# Interface.net
KiCad netlist of a schematic drawn in Altium Designer
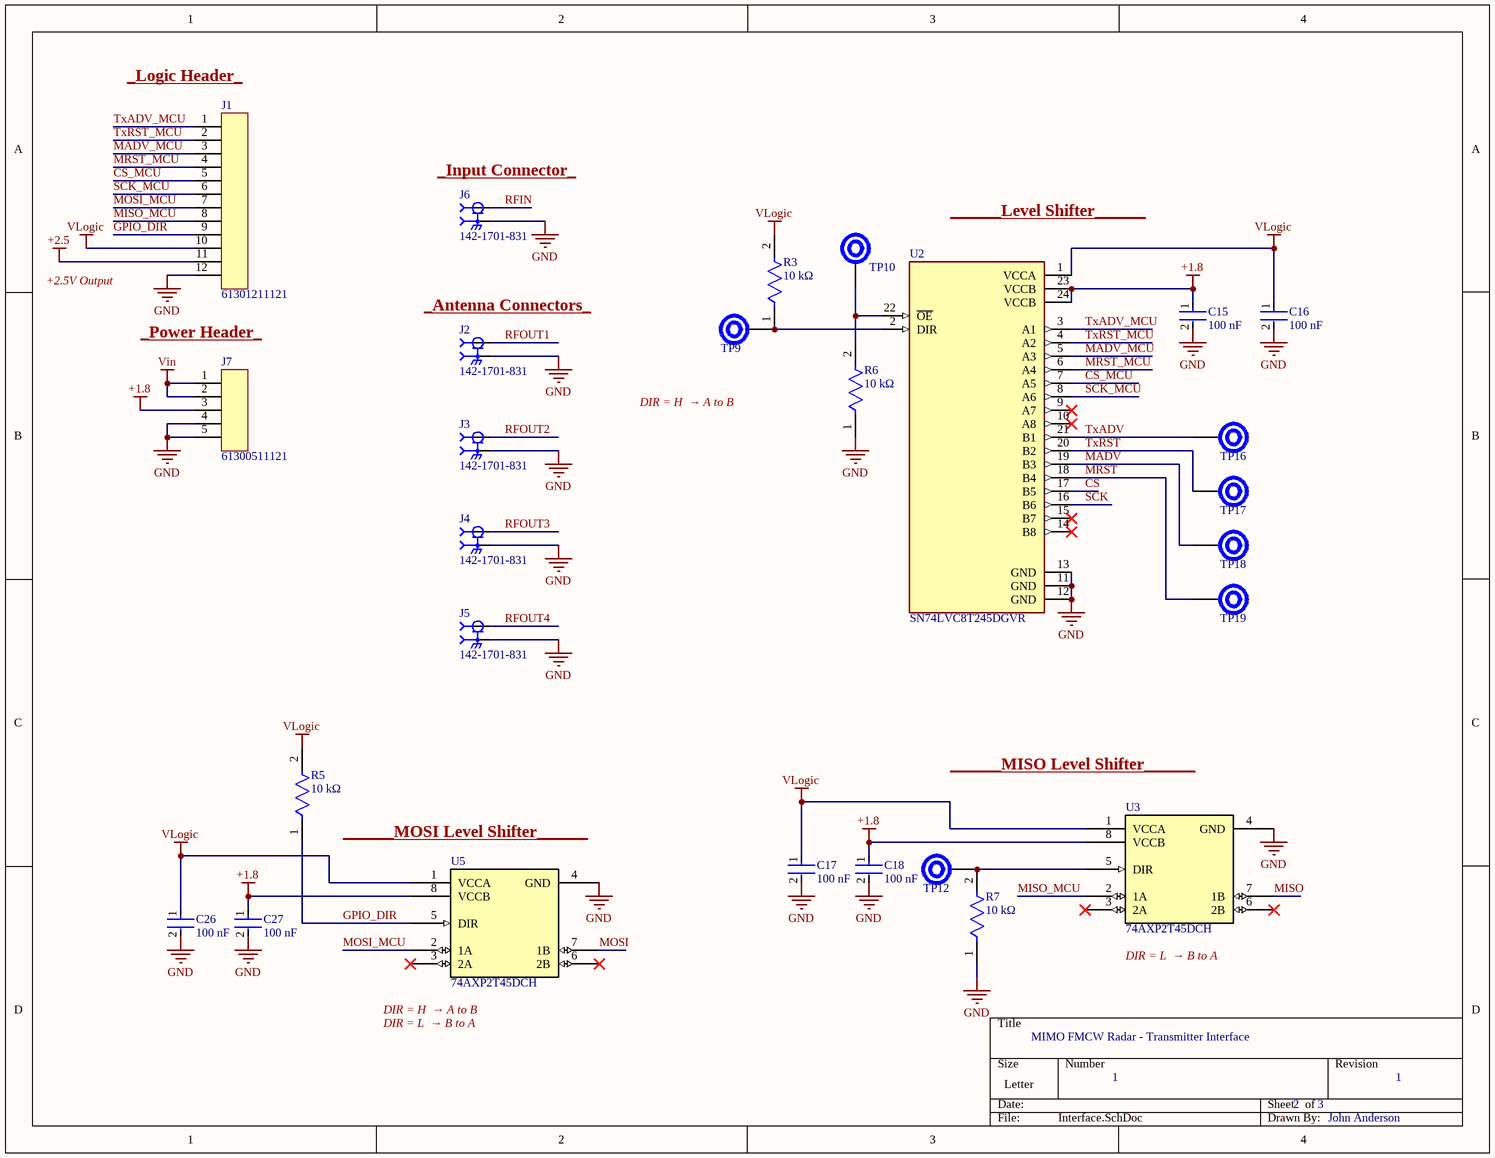
[diagram p0: Interface.SchDoc]

(export (version "E")
  (design (tool "Eeschema 10.0.6"))
  (components
    (comp (ref "C15")
      (value "100 nF")
      (footprint "FP-CGA3E-0_3-0_1-MFG")
      (libsource (lib "Power Pullers") (part "b4654b650e69147ec39a6b967a45e02"))
    )
    (comp (ref "C16")
      (value "100 nF")
      (footprint "FP-CGA3E-0_3-0_1-MFG")
      (libsource (lib "Power Pullers") (part "b4654b650e69147ec39a6b967a45e02"))
    )
    (comp (ref "C17")
      (value "100 nF")
      (footprint "FP-CGA3E-0_3-0_1-MFG")
      (libsource (lib "Power Pullers") (part "b4654b650e69147ec39a6b967a45e02"))
    )
    (comp (ref "C18")
      (value "100 nF")
      (footprint "FP-CGA3E-0_3-0_1-MFG")
      (libsource (lib "Power Pullers") (part "b4654b650e69147ec39a6b967a45e02"))
    )
    (comp (ref "C26")
      (value "100 nF")
      (footprint "FP-CGA3E-0_3-0_1-MFG")
      (libsource (lib "Power Pullers") (part "b4654b650e69147ec39a6b967a45e02"))
    )
    (comp (ref "C27")
      (value "100 nF")
      (footprint "FP-CGA3E-0_3-0_1-MFG")
      (libsource (lib "Power Pullers") (part "b4654b650e69147ec39a6b967a45e02"))
    )
    (comp (ref "J1")
      (value "61301211121")
      (footprint "61301211121")
      (description "THT Vertical Pin Header WR-PHD, Pitch 2.54 mm, Single Row, 12 pins")
      (libsource (lib "Power Pullers") (part "Header_Male_1R_12P"))
    )
    (comp (ref "J2")
      (value "142-1701-831")
      (footprint "142-1701-831-Footprint-1")
      (description "RF SMA Connector, 1 Contact(s), Female, Board Mount, Surface Mount Terminal, Locking, Jack")
      (libsource (lib "Power Pullers") (part "142-1701-831-Symbol-1"))
    )
    (comp (ref "J3")
      (value "142-1701-831")
      (footprint "142-1701-831-Footprint-1")
      (description "RF SMA Connector, 1 Contact(s), Female, Board Mount, Surface Mount Terminal, Locking, Jack")
      (libsource (lib "Power Pullers") (part "142-1701-831-Symbol-1"))
    )
    (comp (ref "J4")
      (value "142-1701-831")
      (footprint "142-1701-831-Footprint-1")
      (description "RF SMA Connector, 1 Contact(s), Female, Board Mount, Surface Mount Terminal, Locking, Jack")
      (libsource (lib "Power Pullers") (part "142-1701-831-Symbol-1"))
    )
    (comp (ref "J5")
      (value "142-1701-831")
      (footprint "142-1701-831-Footprint-1")
      (description "RF SMA Connector, 1 Contact(s), Female, Board Mount, Surface Mount Terminal, Locking, Jack")
      (libsource (lib "Power Pullers") (part "142-1701-831-Symbol-1"))
    )
    (comp (ref "J6")
      (value "142-1701-831")
      (footprint "142-1701-831-Footprint-1")
      (description "RF SMA Connector, 1 Contact(s), Female, Board Mount, Surface Mount Terminal, Locking, Jack")
      (libsource (lib "Power Pullers") (part "142-1701-831-Symbol-1"))
    )
    (comp (ref "J7")
      (value "61300511121")
      (footprint "61300511121")
      (description "THT Vertical Pin Header WR-PHD, Pitch 2.54 mm, Single Row, 5 pins")
      (libsource (lib "Power Pullers") (part "Header_Male_1R_05P"))
    )
    (comp (ref "R3")
      (value "10 kΩ")
      (footprint "FP-RC0603-0_55-IPC_C")
      (fields (field (name "POWER") "100mW") (field (name "TOLERANCE") "1%"))
      (libsource (lib "Power Pullers") (part "1029c3af85768c4190bb7ad29bc67b5"))
    )
    (comp (ref "R5")
      (value "10 kΩ")
      (footprint "FP-RC0603-0_55-IPC_C")
      (fields (field (name "POWER") "100mW") (field (name "TOLERANCE") "1%"))
      (libsource (lib "Power Pullers") (part "1029c3af85768c4190bb7ad29bc67b5"))
    )
    (comp (ref "R6")
      (value "10 kΩ")
      (footprint "FP-RC0603-0_55-IPC_C")
      (fields (field (name "POWER") "100mW") (field (name "TOLERANCE") "1%"))
      (libsource (lib "Power Pullers") (part "1029c3af85768c4190bb7ad29bc67b5"))
    )
    (comp (ref "R7")
      (value "10 kΩ")
      (footprint "FP-RC0603-0_55-IPC_C")
      (fields (field (name "POWER") "100mW") (field (name "TOLERANCE") "1%"))
      (libsource (lib "Power Pullers") (part "1029c3af85768c4190bb7ad29bc67b5"))
    )
    (comp (ref "TP9")
      (value "Test Point - 32 mil")
      (footprint "Test Point - 32 mil-Footprint-1")
      (description "32 mil (0.8 mm) test point.")
      (libsource (lib "Power Pullers") (part "Test Point - 32 mil-Symbol-1"))
    )
    (comp (ref "TP10")
      (value "Test Point - 32 mil")
      (footprint "Test Point - 32 mil-Footprint-1")
      (description "32 mil (0.8 mm) test point.")
      (libsource (lib "Power Pullers") (part "Test Point - 32 mil-Symbol-1"))
    )
    (comp (ref "TP12")
      (value "Test Point - 32 mil")
      (footprint "Test Point - 32 mil-Footprint-1")
      (description "32 mil (0.8 mm) test point.")
      (libsource (lib "Power Pullers") (part "Test Point - 32 mil-Symbol-1"))
    )
    (comp (ref "TP16")
      (value "Test Point - 32 mil")
      (footprint "Test Point - 32 mil-Footprint-1")
      (description "32 mil (0.8 mm) test point.")
      (libsource (lib "Power Pullers") (part "Test Point - 32 mil-Symbol-1"))
    )
    (comp (ref "TP17")
      (value "Test Point - 32 mil")
      (footprint "Test Point - 32 mil-Footprint-1")
      (description "32 mil (0.8 mm) test point.")
      (libsource (lib "Power Pullers") (part "Test Point - 32 mil-Symbol-1"))
    )
    (comp (ref "TP18")
      (value "Test Point - 32 mil")
      (footprint "Test Point - 32 mil-Footprint-1")
      (description "32 mil (0.8 mm) test point.")
      (libsource (lib "Power Pullers") (part "Test Point - 32 mil-Symbol-1"))
    )
    (comp (ref "TP19")
      (value "Test Point - 32 mil")
      (footprint "Test Point - 32 mil-Footprint-1")
      (description "32 mil (0.8 mm) test point.")
      (libsource (lib "Power Pullers") (part "Test Point - 32 mil-Symbol-1"))
    )
    (comp (ref "U2")
      (value "SN74LVC8T245DGVR")
      (footprint "SN74LVC8T245DGVR-Footprint-1")
      (description "IC BUS TRANSCVR 8BIT 24TVSOP / Voltage Level Translator 8-CH Bidirectional 24-Pin TVSOP T/R")
      (libsource (lib "Power Pullers") (part "SN74LVC8T245DGVR-Symbol-1"))
    )
    (comp (ref "U3")
      (value "74AXP2T45DCH")
      (footprint "74AXP2T45DCH-Footprint-1")
      (description "Dual Supply Level Translator 2-bit Bidirectional 0.95V to 5.5V 8-Pin VSSOP")
      (libsource (lib "Power Pullers") (part "74AXP2T45DCH-Symbol-1"))
    )
    (comp (ref "U5")
      (value "74AXP2T45DCH")
      (footprint "74AXP2T45DCH-Footprint-1")
      (description "Dual Supply Level Translator 2-bit Bidirectional 0.95V to 5.5V 8-Pin VSSOP")
      (libsource (lib "Power Pullers") (part "74AXP2T45DCH-Symbol-1"))
    )
  )
  (nets
    (net (code "1") (name "+1.8") (class "Default")
      (node (ref "C15") (pin "1") (pinfunction "1_1") (pintype "passive"))
      (node (ref "C18") (pin "1") (pinfunction "1_1") (pintype "passive"))
      (node (ref "C27") (pin "1") (pinfunction "1_1") (pintype "passive"))
      (node (ref "J7") (pin "3") (pinfunction "3_3") (pintype "passive"))
      (node (ref "U2") (pin "23") (pinfunction "VCCB_23") (pintype "power_in"))
      (node (ref "U2") (pin "24") (pinfunction "VCCB_24") (pintype "power_in"))
      (node (ref "U3") (pin "8") (pinfunction "VCCB_8") (pintype "power_in"))
      (node (ref "U5") (pin "8") (pinfunction "VCCB_8") (pintype "power_in"))
    )
    (net (code "2") (name "+2.5") (class "Default")
      (node (ref "J1") (pin "11") (pinfunction "11_11") (pintype "passive"))
    )
    (net (code "3") (name "/CS") (class "Default")
      (node (ref "U2") (pin "17") (pinfunction "B5_17") (pintype "output"))
    )
    (net (code "4") (name "/CS_MCU") (class "Default")
      (node (ref "J1") (pin "5") (pinfunction "5_5") (pintype "passive"))
      (node (ref "U2") (pin "7") (pinfunction "A5_7") (pintype "output"))
    )
    (net (code "5") (name "/GPIO_DIR") (class "Default")
      (node (ref "J1") (pin "9") (pinfunction "9_9") (pintype "passive"))
      (node (ref "R5") (pin "1") (pinfunction "1_1") (pintype "passive"))
      (node (ref "U5") (pin "5") (pinfunction "DIR_5") (pintype "input"))
    )
    (net (code "6") (name "/MADV") (class "Default")
      (node (ref "TP18") (pin "1") (pinfunction "1_1") (pintype "passive"))
      (node (ref "U2") (pin "19") (pinfunction "B3_19") (pintype "output"))
    )
    (net (code "7") (name "/MADV_MCU") (class "Default")
      (node (ref "J1") (pin "3") (pinfunction "3_3") (pintype "passive"))
      (node (ref "U2") (pin "5") (pinfunction "A3_5") (pintype "output"))
    )
    (net (code "8") (name "/MISO") (class "Default")
      (node (ref "U3") (pin "7") (pinfunction "1B_7") (pintype "bidirectional"))
    )
    (net (code "9") (name "/MISO_MCU") (class "Default")
      (node (ref "J1") (pin "8") (pinfunction "8_8") (pintype "passive"))
      (node (ref "U3") (pin "2") (pinfunction "1A_2") (pintype "bidirectional"))
    )
    (net (code "10") (name "/MOSI") (class "Default")
      (node (ref "U5") (pin "7") (pinfunction "1B_7") (pintype "bidirectional"))
    )
    (net (code "11") (name "/MOSI_MCU") (class "Default")
      (node (ref "J1") (pin "7") (pinfunction "7_7") (pintype "passive"))
      (node (ref "U5") (pin "2") (pinfunction "1A_2") (pintype "bidirectional"))
    )
    (net (code "12") (name "/MRST") (class "Default")
      (node (ref "TP19") (pin "1") (pinfunction "1_1") (pintype "passive"))
      (node (ref "U2") (pin "18") (pinfunction "B4_18") (pintype "output"))
    )
    (net (code "13") (name "/MRST_MCU") (class "Default")
      (node (ref "J1") (pin "4") (pinfunction "4_4") (pintype "passive"))
      (node (ref "U2") (pin "6") (pinfunction "A4_6") (pintype "output"))
    )
    (net (code "14") (name "/RFIN") (class "Default")
      (node (ref "J6") (pin "1") (pinfunction "SIG_1") (pintype "passive"))
    )
    (net (code "15") (name "/RFOUT1") (class "Default")
      (node (ref "J2") (pin "1") (pinfunction "SIG_1") (pintype "passive"))
    )
    (net (code "16") (name "/RFOUT2") (class "Default")
      (node (ref "J3") (pin "1") (pinfunction "SIG_1") (pintype "passive"))
    )
    (net (code "17") (name "/RFOUT3") (class "Default")
      (node (ref "J4") (pin "1") (pinfunction "SIG_1") (pintype "passive"))
    )
    (net (code "18") (name "/RFOUT4") (class "Default")
      (node (ref "J5") (pin "1") (pinfunction "SIG_1") (pintype "passive"))
    )
    (net (code "19") (name "/SCK") (class "Default")
      (node (ref "U2") (pin "16") (pinfunction "B6_16") (pintype "output"))
    )
    (net (code "20") (name "/SCK_MCU") (class "Default")
      (node (ref "J1") (pin "6") (pinfunction "6_6") (pintype "passive"))
      (node (ref "U2") (pin "8") (pinfunction "A6_8") (pintype "output"))
    )
    (net (code "21") (name "/TxADV") (class "Default")
      (node (ref "TP16") (pin "1") (pinfunction "1_1") (pintype "passive"))
      (node (ref "U2") (pin "21") (pinfunction "B1_21") (pintype "output"))
    )
    (net (code "22") (name "/TxADV_MCU") (class "Default")
      (node (ref "J1") (pin "1") (pinfunction "1_1") (pintype "passive"))
      (node (ref "U2") (pin "3") (pinfunction "A1_3") (pintype "output"))
    )
    (net (code "23") (name "/TxRST") (class "Default")
      (node (ref "TP17") (pin "1") (pinfunction "1_1") (pintype "passive"))
      (node (ref "U2") (pin "20") (pinfunction "B2_20") (pintype "output"))
    )
    (net (code "24") (name "/TxRST_MCU") (class "Default")
      (node (ref "J1") (pin "2") (pinfunction "2_2") (pintype "passive"))
      (node (ref "U2") (pin "4") (pinfunction "A2_4") (pintype "output"))
    )
    (net (code "25") (name "GND") (class "Default")
      (node (ref "C15") (pin "2") (pinfunction "2_2") (pintype "passive"))
      (node (ref "C16") (pin "2") (pinfunction "2_2") (pintype "passive"))
      (node (ref "C17") (pin "2") (pinfunction "2_2") (pintype "passive"))
      (node (ref "C18") (pin "2") (pinfunction "2_2") (pintype "passive"))
      (node (ref "C26") (pin "2") (pinfunction "2_2") (pintype "passive"))
      (node (ref "C27") (pin "2") (pinfunction "2_2") (pintype "passive"))
      (node (ref "J1") (pin "12") (pinfunction "12_12") (pintype "passive"))
      (node (ref "J2") (pin "2") (pinfunction "GND_2") (pintype "power_in"))
      (node (ref "J3") (pin "2") (pinfunction "GND_2") (pintype "power_in"))
      (node (ref "J4") (pin "2") (pinfunction "GND_2") (pintype "power_in"))
      (node (ref "J5") (pin "2") (pinfunction "GND_2") (pintype "power_in"))
      (node (ref "J6") (pin "2") (pinfunction "GND_2") (pintype "power_in"))
      (node (ref "J7") (pin "4") (pinfunction "4_4") (pintype "passive"))
      (node (ref "J7") (pin "5") (pinfunction "5_5") (pintype "passive"))
      (node (ref "R6") (pin "1") (pinfunction "1_1") (pintype "passive"))
      (node (ref "R7") (pin "1") (pinfunction "1_1") (pintype "passive"))
      (node (ref "U2") (pin "11") (pinfunction "GND_11") (pintype "power_in"))
      (node (ref "U2") (pin "12") (pinfunction "GND_12") (pintype "power_in"))
      (node (ref "U2") (pin "13") (pinfunction "GND_13") (pintype "power_in"))
      (node (ref "U3") (pin "4") (pinfunction "GND_4") (pintype "power_in"))
      (node (ref "U5") (pin "4") (pinfunction "GND_4") (pintype "power_in"))
    )
    (net (code "26") (name "Net-(U2-DIR)") (class "Default")
      (node (ref "R3") (pin "1") (pinfunction "1_1") (pintype "passive"))
      (node (ref "TP9") (pin "1") (pinfunction "1_1") (pintype "passive"))
      (node (ref "U2") (pin "2") (pinfunction "DIR_2") (pintype "input"))
    )
    (net (code "27") (name "Net-(U2-~{OE})") (class "Default")
      (node (ref "R6") (pin "2") (pinfunction "2_2") (pintype "passive"))
      (node (ref "TP10") (pin "1") (pinfunction "1_1") (pintype "passive"))
      (node (ref "U2") (pin "22") (pinfunction "~{OE}_22") (pintype "input"))
    )
    (net (code "28") (name "Net-(U3-DIR)") (class "Default")
      (node (ref "R7") (pin "2") (pinfunction "2_2") (pintype "passive"))
      (node (ref "TP12") (pin "1") (pinfunction "1_1") (pintype "passive"))
      (node (ref "U3") (pin "5") (pinfunction "DIR_5") (pintype "input"))
    )
    (net (code "29") (name "VLogic") (class "Default")
      (node (ref "C16") (pin "1") (pinfunction "1_1") (pintype "passive"))
      (node (ref "C17") (pin "1") (pinfunction "1_1") (pintype "passive"))
      (node (ref "C26") (pin "1") (pinfunction "1_1") (pintype "passive"))
      (node (ref "J1") (pin "10") (pinfunction "10_10") (pintype "passive"))
      (node (ref "R3") (pin "2") (pinfunction "2_2") (pintype "passive"))
      (node (ref "R5") (pin "2") (pinfunction "2_2") (pintype "passive"))
      (node (ref "U2") (pin "1") (pinfunction "VCCA_1") (pintype "power_in"))
      (node (ref "U3") (pin "1") (pinfunction "VCCA_1") (pintype "power_in"))
      (node (ref "U5") (pin "1") (pinfunction "VCCA_1") (pintype "power_in"))
    )
    (net (code "30") (name "Vin") (class "Default")
      (node (ref "J7") (pin "1") (pinfunction "1_1") (pintype "passive"))
      (node (ref "J7") (pin "2") (pinfunction "2_2") (pintype "passive"))
    )
    (net (code "31") (name "unconnected-(U2-A7-Pad9)") (class "Default")
      (node (ref "U2") (pin "9") (pinfunction "A7_9") (pintype "output+no_connect"))
    )
    (net (code "32") (name "unconnected-(U2-A8-Pad10)") (class "Default")
      (node (ref "U2") (pin "10") (pinfunction "A8_10") (pintype "output+no_connect"))
    )
    (net (code "33") (name "unconnected-(U2-B7-Pad15)") (class "Default")
      (node (ref "U2") (pin "15") (pinfunction "B7_15") (pintype "output+no_connect"))
    )
    (net (code "34") (name "unconnected-(U2-B8-Pad14)") (class "Default")
      (node (ref "U2") (pin "14") (pinfunction "B8_14") (pintype "output+no_connect"))
    )
    (net (code "35") (name "unconnected-(U3-2A-Pad3)") (class "Default")
      (node (ref "U3") (pin "3") (pinfunction "2A_3") (pintype "bidirectional+no_connect"))
    )
    (net (code "36") (name "unconnected-(U3-2B-Pad6)") (class "Default")
      (node (ref "U3") (pin "6") (pinfunction "2B_6") (pintype "bidirectional+no_connect"))
    )
    (net (code "37") (name "unconnected-(U5-2A-Pad3)") (class "Default")
      (node (ref "U5") (pin "3") (pinfunction "2A_3") (pintype "bidirectional+no_connect"))
    )
    (net (code "38") (name "unconnected-(U5-2B-Pad6)") (class "Default")
      (node (ref "U5") (pin "6") (pinfunction "2B_6") (pintype "bidirectional+no_connect"))
    )
  )
)
